# 02-Power.net
KiCad netlist of a schematic drawn in Altium Designer
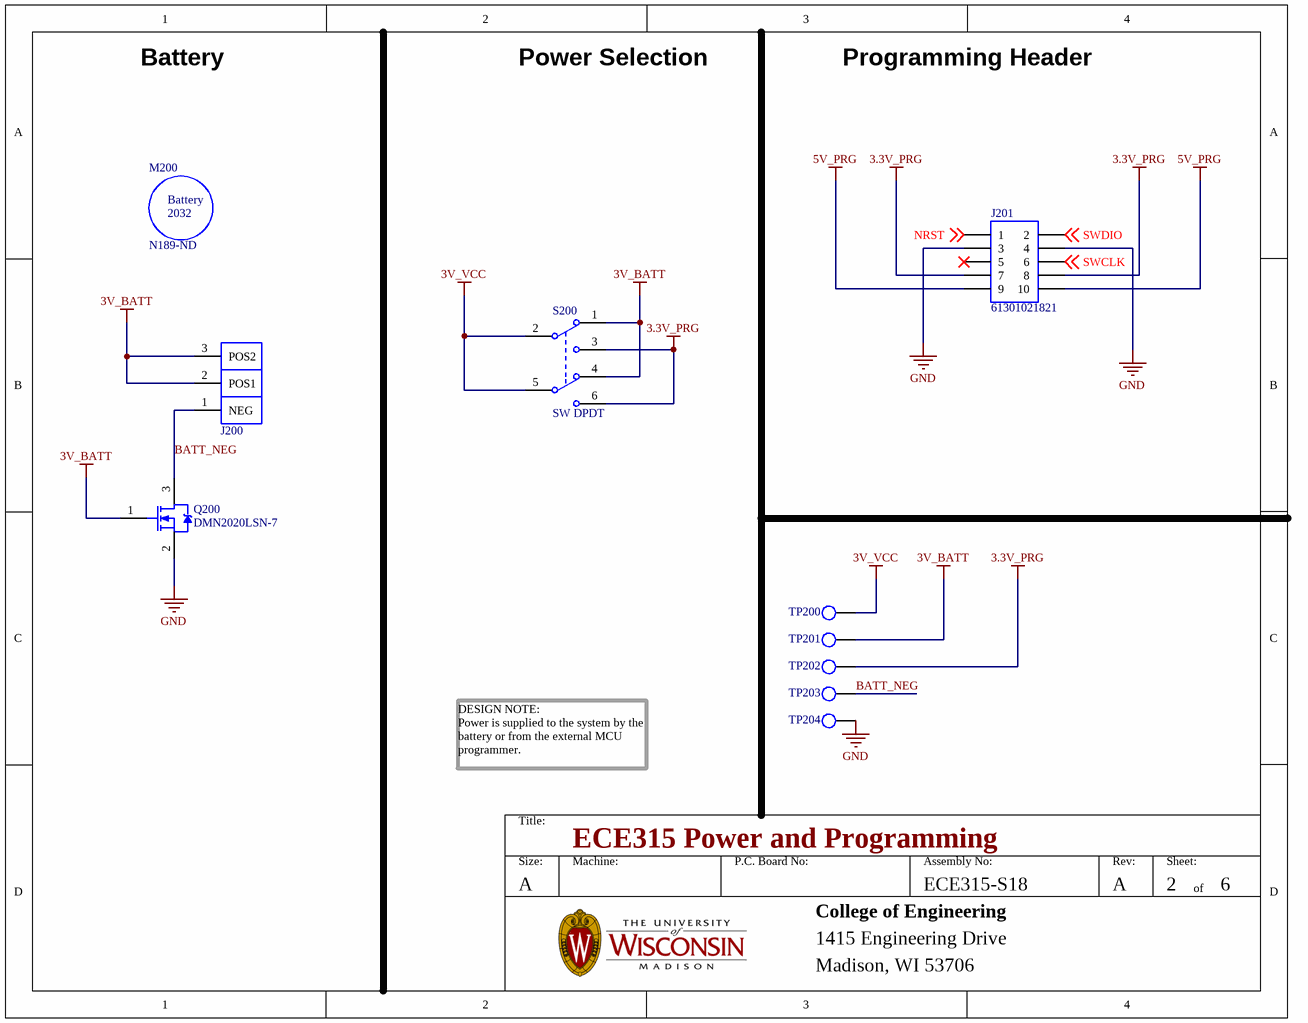
[diagram p0: 02-Power.SchDoc]

(export (version "E")
  (design (tool "Eeschema 10.0.6"))
  (components
    (comp (ref "J200")
      (value "CONN_BAT_2032")
      (footprint "BATT_2032")
      (description "HOLDER BATTERY 20MM COIN")
      (fields (field (name "MANUFACTURER") "Linx") (field (name "MANUFACTURER PART NUMBER") "BAT-HLD-001"))
      (libsource (lib "ece315") (part "CONN_BAT_2032"))
    )
    (comp (ref "J201")
      (value "CONN_ST_PROGRAMMER")
      (footprint "HDR_5x2")
      (description "CONN HEADER 2.54MM 10POS GOLD")
      (fields
        (field (name "MANUFACTURER") "Wurth Electronics Inc.")
        (field (name "MANUFACTURER PART NUMBER") "61301021821")
      )
      (libsource (lib "ece315") (part "CONN_ST_PROGRAMMER"))
    )
    (comp (ref "M200")
      (value "BATTERY_2032")
      (fields
        (field (name "MANUFACTURER") "Energizer")
        (field (name "MANUFACTURER PART NUMBER") "CR2032VP")
        (field (name "SUPPLIER PART NUMBER 1") "N189-ND")
      )
      (libsource (lib "ece315") (part "BATTERY_2032"))
    )
    (comp (ref "Q200")
      (value "IC_NMOS_DMN2020LSN")
      (footprint "SOT23")
      (fields (field (name "MANUFACTURER") "Diodes") (field (name "MANUFACTURER PART NUMBER") "DMN2020LSN-7"))
      (libsource (lib "ece315") (part "IC_NMOS_DMN2020LSN"))
    )
    (comp (ref "S200")
      (value "SW DPDT")
      (footprint "DPDT")
      (description "Switch")
      (fields
        (field (name "MANUFACTURER") "ITT /  C&K Components")
        (field (name "MANUFACTURER PART NUMBER") "JS202011SCQN")
        (field (name "PUBLISHER") "Altium Limited")
      )
      (libsource (lib "ece315") (part "SW DPDT"))
    )
    (comp (ref "TP200")
      (value "TP_1206")
      (footprint "TP-SMC-1206")
      (description "Test Point SMD 1206")
      (fields
        (field (name "MANUFACTURER") "TE Connectivity (Tyco Electronics)")
        (field (name "MANUFACTURER PART NUMBER") "1625854-1")
      )
      (libsource (lib "ece315-2017-fall") (part "TP_1206"))
    )
    (comp (ref "TP201")
      (value "TP_1206")
      (footprint "TP-SMC-1206")
      (description "Test Point SMD 1206")
      (fields
        (field (name "MANUFACTURER") "TE Connectivity (Tyco Electronics)")
        (field (name "MANUFACTURER PART NUMBER") "1625854-1")
      )
      (libsource (lib "ece315-2017-fall") (part "TP_1206"))
    )
    (comp (ref "TP202")
      (value "TP_1206")
      (footprint "TP-SMC-1206")
      (description "Test Point SMD 1206")
      (fields
        (field (name "MANUFACTURER") "TE Connectivity (Tyco Electronics)")
        (field (name "MANUFACTURER PART NUMBER") "1625854-1")
      )
      (libsource (lib "ece315-2017-fall") (part "TP_1206"))
    )
    (comp (ref "TP203")
      (value "TP_1206")
      (footprint "TP-SMC-1206")
      (description "Test Point SMD 1206")
      (fields
        (field (name "MANUFACTURER") "TE Connectivity (Tyco Electronics)")
        (field (name "MANUFACTURER PART NUMBER") "1625854-1")
      )
      (libsource (lib "ece315-2017-fall") (part "TP_1206"))
    )
    (comp (ref "TP204")
      (value "TP_1206")
      (footprint "TP-SMC-1206")
      (description "Test Point SMD 1206")
      (fields
        (field (name "MANUFACTURER") "TE Connectivity (Tyco Electronics)")
        (field (name "MANUFACTURER PART NUMBER") "1625854-1")
      )
      (libsource (lib "ece315-2017-fall") (part "TP_1206"))
    )
  )
  (nets
    (net (code "1") (name "/BATT_NEG") (class "Default")
      (node (ref "J200") (pin "1") (pinfunction "NEG_1") (pintype "passive"))
      (node (ref "Q200") (pin "3") (pinfunction "3_3") (pintype "passive"))
      (node (ref "TP203") (pin "1") (pintype "passive"))
    )
    (net (code "2") (name "3.3V_PRG") (class "Default")
      (node (ref "J201") (pin "7") (pinfunction "7_7") (pintype "passive"))
      (node (ref "J201") (pin "8") (pinfunction "8_8") (pintype "passive"))
      (node (ref "S200") (pin "3") (pinfunction "NO1_3") (pintype "passive"))
      (node (ref "S200") (pin "6") (pinfunction "NO2_6") (pintype "passive"))
      (node (ref "TP202") (pin "1") (pintype "passive"))
    )
    (net (code "3") (name "3V_BATT") (class "Default")
      (node (ref "J200") (pin "2") (pinfunction "POS1_2") (pintype "passive"))
      (node (ref "J200") (pin "3") (pinfunction "POS2_3") (pintype "passive"))
      (node (ref "Q200") (pin "1") (pinfunction "1_1") (pintype "passive"))
      (node (ref "S200") (pin "1") (pinfunction "NC1_1") (pintype "passive"))
      (node (ref "S200") (pin "4") (pinfunction "NC2_4") (pintype "passive"))
      (node (ref "TP201") (pin "1") (pintype "passive"))
    )
    (net (code "4") (name "3V_VCC") (class "Default")
      (node (ref "S200") (pin "2") (pinfunction "COMMON1_2") (pintype "passive"))
      (node (ref "S200") (pin "5") (pinfunction "COMMON2_5") (pintype "passive"))
      (node (ref "TP200") (pin "1") (pintype "passive"))
    )
    (net (code "5") (name "5V_PRG") (class "Default")
      (node (ref "J201") (pin "10") (pinfunction "10_10") (pintype "passive"))
      (node (ref "J201") (pin "9") (pinfunction "9_9") (pintype "passive"))
    )
    (net (code "6") (name "GND") (class "Default")
      (node (ref "J201") (pin "3") (pinfunction "3_3") (pintype "passive"))
      (node (ref "J201") (pin "4") (pinfunction "4_4") (pintype "passive"))
      (node (ref "Q200") (pin "2") (pinfunction "2_2") (pintype "passive"))
      (node (ref "TP204") (pin "1") (pintype "passive"))
    )
    (net (code "7") (name "NRST") (class "Default")
      (node (ref "J201") (pin "1") (pinfunction "1_1") (pintype "passive"))
    )
    (net (code "8") (name "SWCLK") (class "Default")
      (node (ref "J201") (pin "6") (pinfunction "6_6") (pintype "passive"))
    )
    (net (code "9") (name "SWDIO") (class "Default")
      (node (ref "J201") (pin "2") (pinfunction "2_2") (pintype "passive"))
    )
    (net (code "10") (name "unconnected-(J201-Pad5)") (class "Default")
      (node (ref "J201") (pin "5") (pinfunction "5_5") (pintype "passive+no_connect"))
    )
  )
)
